# Power.net
KiCad netlist of a schematic drawn in Altium Designer
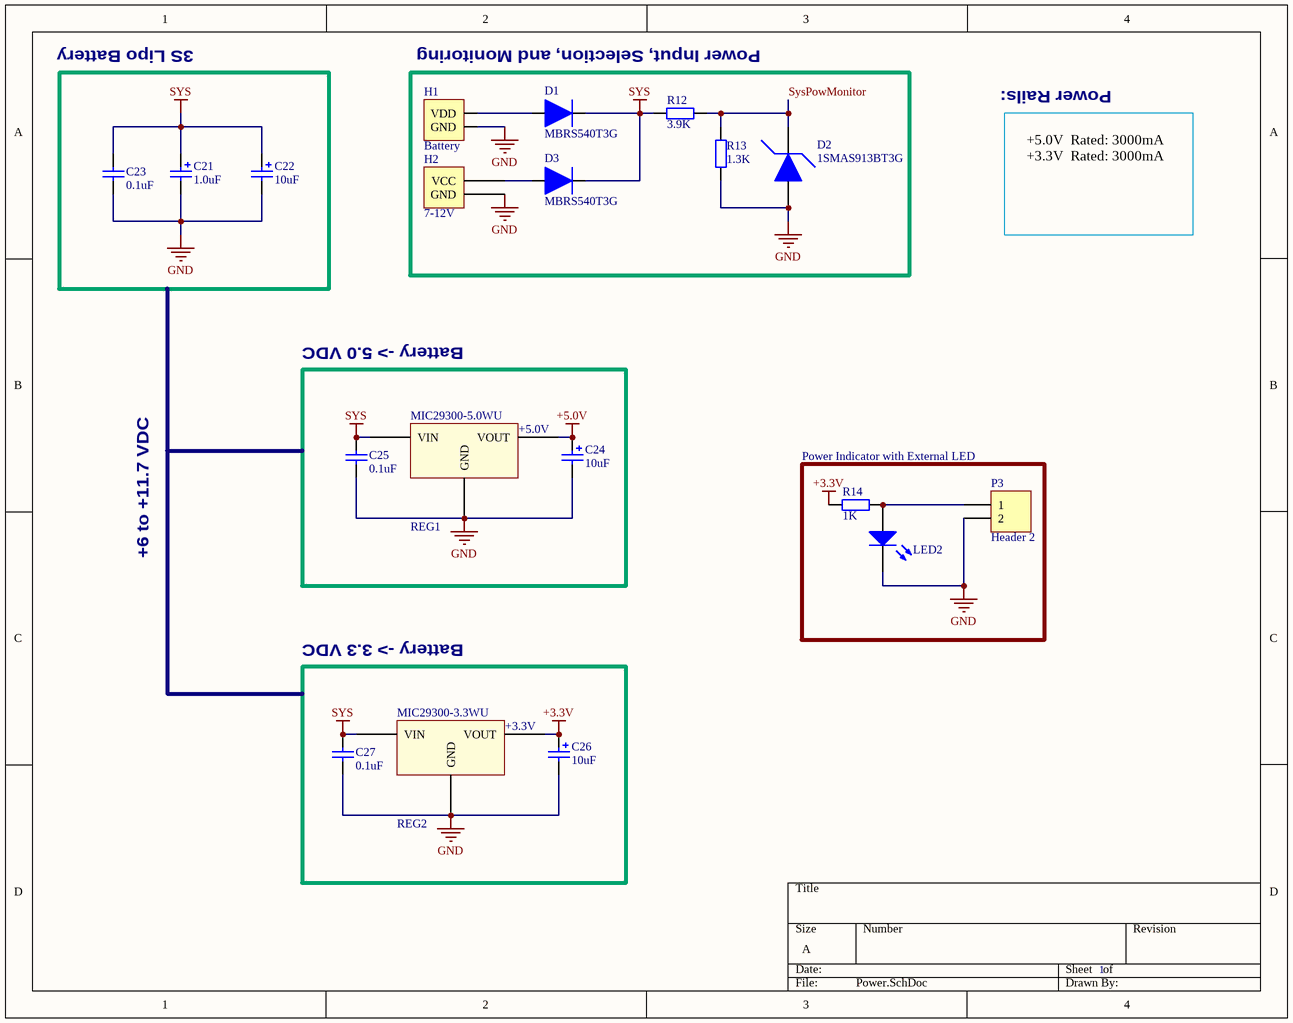
[diagram p0: Power.SchDoc]

(export (version "E")
  (design (tool "Eeschema 10.0.6"))
  (components
    (comp (ref "C21")
      (value "1.0uF")
      (footprint "Capacitor - Tantalum Case A")
      (description "Tantalum Capacitor - Case A")
      (fields (field (name "Comment") "1.0uF Low-ESR Tantalum CaseA"))
      (libsource (lib "Ad-Flier_Parts") (part "SMD_Cap_Tantalum"))
    )
    (comp (ref "C22")
      (value "10uF")
      (footprint "CAPPR2-5x5")
      (description "Polarized Capacitor (Radial)")
      (fields (field (name "Comment") "10uF Electrolitic") (field (name "PUBLISHER") "Altium Limited"))
      (libsource (lib "Miscellaneous Devices") (part "Cap Pol1"))
    )
    (comp (ref "C23")
      (value "0.1uF")
      (footprint "SMD 1206")
      (description "Capacitor")
      (fields (field (name "Comment") "0.1uF SMD 1206"))
      (libsource (lib "Miscellaneous Devices") (part "Cap"))
    )
    (comp (ref "C24")
      (value "10uF")
      (footprint "Capacitor - Tantalum Case A")
      (description "Tantalum Capacitor - Case A")
      (fields (field (name "Comment") "10uF Low-ESR Tantalum CaseA"))
      (libsource (lib "Ad-Flier_Parts") (part "SMD_Cap_Tantalum"))
    )
    (comp (ref "C25")
      (value "0.1uF")
      (footprint "SMD 1206")
      (description "Capacitor")
      (fields (field (name "Comment") "0.1uF SMD 1206"))
      (libsource (lib "Miscellaneous Devices") (part "Cap"))
    )
    (comp (ref "C26")
      (value "10uF")
      (footprint "Capacitor - Tantalum Case A")
      (description "Tantalum Capacitor - Case A")
      (fields (field (name "Comment") "10uF Low-ESR Tantalum CaseA"))
      (libsource (lib "Ad-Flier_Parts") (part "SMD_Cap_Tantalum"))
    )
    (comp (ref "C27")
      (value "0.1uF")
      (footprint "SMD 1206")
      (description "Capacitor")
      (fields (field (name "Comment") "0.1uF SMD 1206"))
      (libsource (lib "Miscellaneous Devices") (part "Cap"))
    )
    (comp (ref "D1")
      (value "MBRS540T3G")
      (footprint "MBRS540T3G")
      (description "40V 5A Scottky Diode")
      (libsource (lib "Ad-Flier_Parts") (part "MBRS540T3G"))
    )
    (comp (ref "D2")
      (value "1SMAS913BT3G")
      (footprint "1SMA5913BT3G")
      (description "3.3V 1.5W Zener Diode")
      (libsource (lib "Ad-Flier_Parts") (part "1SMAS913BT3G"))
    )
    (comp (ref "D3")
      (value "MBRS540T3G")
      (footprint "MBRS540T3G")
      (description "40V 5A Scottky Diode")
      (libsource (lib "Ad-Flier_Parts") (part "MBRS540T3G"))
    )
    (comp (ref "H1")
      (value "Battery")
      (footprint "PC Wire Connector")
      (libsource (lib "Ad-Flier_Parts") (part "PC Wire Connector"))
    )
    (comp (ref "H2")
      (value "7-12V")
      (footprint "DC Power Jack")
      (description "DC Power Jack")
      (libsource (lib "Ad-Flier_Parts") (part "DC Jack"))
    )
    (comp (ref "LED2")
      (value "ON")
      (footprint "PLCC-4 LED")
      (description "Surface Mount Chip LED")
      (libsource (lib "Ad-Flier_Parts") (part "LED PLCC-4"))
    )
    (comp (ref "P3")
      (value "Header 2")
      (footprint "HDR1X2")
      (description "Header, 2-Pin")
      (fields (field (name "PUBLISHER") "Altium Limited"))
      (libsource (lib "Miscellaneous Connectors") (part "Header 2"))
    )
    (comp (ref "R12")
      (value "3.9K")
      (footprint "RES12.2-8.5X3.3")
      (description "Resistor")
      (fields (field (name "Comment") "3.9K Radial"))
      (libsource (lib "Miscellaneous Devices") (part "Res2"))
    )
    (comp (ref "R13")
      (value "1.3K")
      (footprint "RES12.2-8.5X3.3")
      (description "Resistor")
      (fields (field (name "Comment") "1.3K Radial"))
      (libsource (lib "") (part "Res2_2"))
    )
    (comp (ref "R14")
      (value "1K")
      (footprint "SMD 0805")
      (description "Resistor")
      (fields (field (name "Comment") "1K SMD 0805"))
      (libsource (lib "") (part "Res2_1"))
    )
    (comp (ref "REG1")
      (value "MIC29300-5.0WU")
      (footprint "TO-263 D2PACK")
      (description "3.0A LDO Fixed Volt.(ROHS Compliant)")
      (libsource (lib "Micrel Parts") (part "MIC29300-5.0WU"))
    )
    (comp (ref "REG2")
      (value "MIC29300-3.3WU")
      (footprint "TO-263 D2PACK")
      (description "3.0A LDO Fixed Volt.(ROHS Compliant)")
      (libsource (lib "Micrel Parts") (part "MIC29300-3.3WU"))
    )
  )
  (nets
    (net (code "1") (name "+3.3V") (class "Default")
      (node (ref "C26") (pin "1") (pinfunction "+_1") (pintype "passive"))
      (node (ref "R14") (pin "1") (pinfunction "1_1") (pintype "passive"))
      (node (ref "REG2") (pin "2") (pinfunction "VOUT_2") (pintype "power_in"))
    )
    (net (code "2") (name "+5.0V") (class "Default")
      (node (ref "C24") (pin "1") (pinfunction "+_1") (pintype "passive"))
      (node (ref "REG1") (pin "2") (pinfunction "VOUT_2") (pintype "power_in"))
    )
    (net (code "3") (name "/SysPowMonitor") (class "Default")
      (node (ref "D2") (pin "1") (pinfunction "Out_1") (pintype "passive"))
      (node (ref "R12") (pin "1") (pinfunction "1_1") (pintype "passive"))
      (node (ref "R13") (pin "2") (pinfunction "2_2") (pintype "passive"))
    )
    (net (code "4") (name "GND") (class "Default")
      (node (ref "C21") (pin "2") (pinfunction "-_2") (pintype "passive"))
      (node (ref "C22") (pin "2") (pinfunction "2_2") (pintype "passive"))
      (node (ref "C23") (pin "1") (pinfunction "1_1") (pintype "passive"))
      (node (ref "C24") (pin "2") (pinfunction "-_2") (pintype "passive"))
      (node (ref "C25") (pin "2") (pinfunction "2_2") (pintype "passive"))
      (node (ref "C26") (pin "2") (pinfunction "-_2") (pintype "passive"))
      (node (ref "C27") (pin "1") (pinfunction "1_1") (pintype "passive"))
      (node (ref "D2") (pin "0") (pinfunction "In_0") (pintype "passive"))
      (node (ref "H1") (pin "R") (pinfunction "GND_R") (pintype "passive"))
      (node (ref "H2") (pin "GND") (pinfunction "GND_GND") (pintype "passive"))
      (node (ref "LED2") (pin "2") (pinfunction "K_2") (pintype "passive"))
      (node (ref "P3") (pin "2") (pinfunction "2_2") (pintype "passive"))
      (node (ref "R13") (pin "1") (pinfunction "1_1") (pintype "passive"))
      (node (ref "REG1") (pin "1") (pinfunction "GND_1") (pintype "power_in"))
      (node (ref "REG2") (pin "1") (pinfunction "GND_1") (pintype "power_in"))
    )
    (net (code "5") (name "Net-(D1-In)") (class "Default")
      (node (ref "D1") (pin "0") (pinfunction "In_0") (pintype "passive"))
      (node (ref "H1") (pin "L") (pinfunction "VDD_L") (pintype "passive"))
    )
    (net (code "6") (name "Net-(D3-In)") (class "Default")
      (node (ref "D3") (pin "0") (pinfunction "In_0") (pintype "passive"))
      (node (ref "H2") (pin "VCC") (pinfunction "VCC_VCC") (pintype "passive"))
    )
    (net (code "7") (name "Net-(LED2-A)") (class "Default")
      (node (ref "LED2") (pin "1") (pinfunction "A_1") (pintype "passive"))
      (node (ref "P3") (pin "1") (pinfunction "1_1") (pintype "passive"))
      (node (ref "R14") (pin "2") (pinfunction "2_2") (pintype "passive"))
    )
    (net (code "8") (name "SYS") (class "Default")
      (node (ref "C21") (pin "1") (pinfunction "+_1") (pintype "passive"))
      (node (ref "C22") (pin "1") (pinfunction "1_1") (pintype "passive"))
      (node (ref "C23") (pin "2") (pinfunction "2_2") (pintype "passive"))
      (node (ref "C25") (pin "1") (pinfunction "1_1") (pintype "passive"))
      (node (ref "C27") (pin "2") (pinfunction "2_2") (pintype "passive"))
      (node (ref "D1") (pin "1") (pinfunction "Out_1") (pintype "passive"))
      (node (ref "D3") (pin "1") (pinfunction "Out_1") (pintype "passive"))
      (node (ref "R12") (pin "2") (pinfunction "2_2") (pintype "passive"))
      (node (ref "REG1") (pin "0") (pinfunction "VIN_0") (pintype "power_in"))
      (node (ref "REG2") (pin "0") (pinfunction "VIN_0") (pintype "power_in"))
    )
    (net (code "9") (name "unconnected-(H2-PadNC)") (class "Default")
      (node (ref "H2") (pin "NC") (pinfunction "NC_NC") (pintype "passive"))
    )
  )
)
